# lpc4357-save.net
KiCad netlist of a schematic drawn in Altium Designer
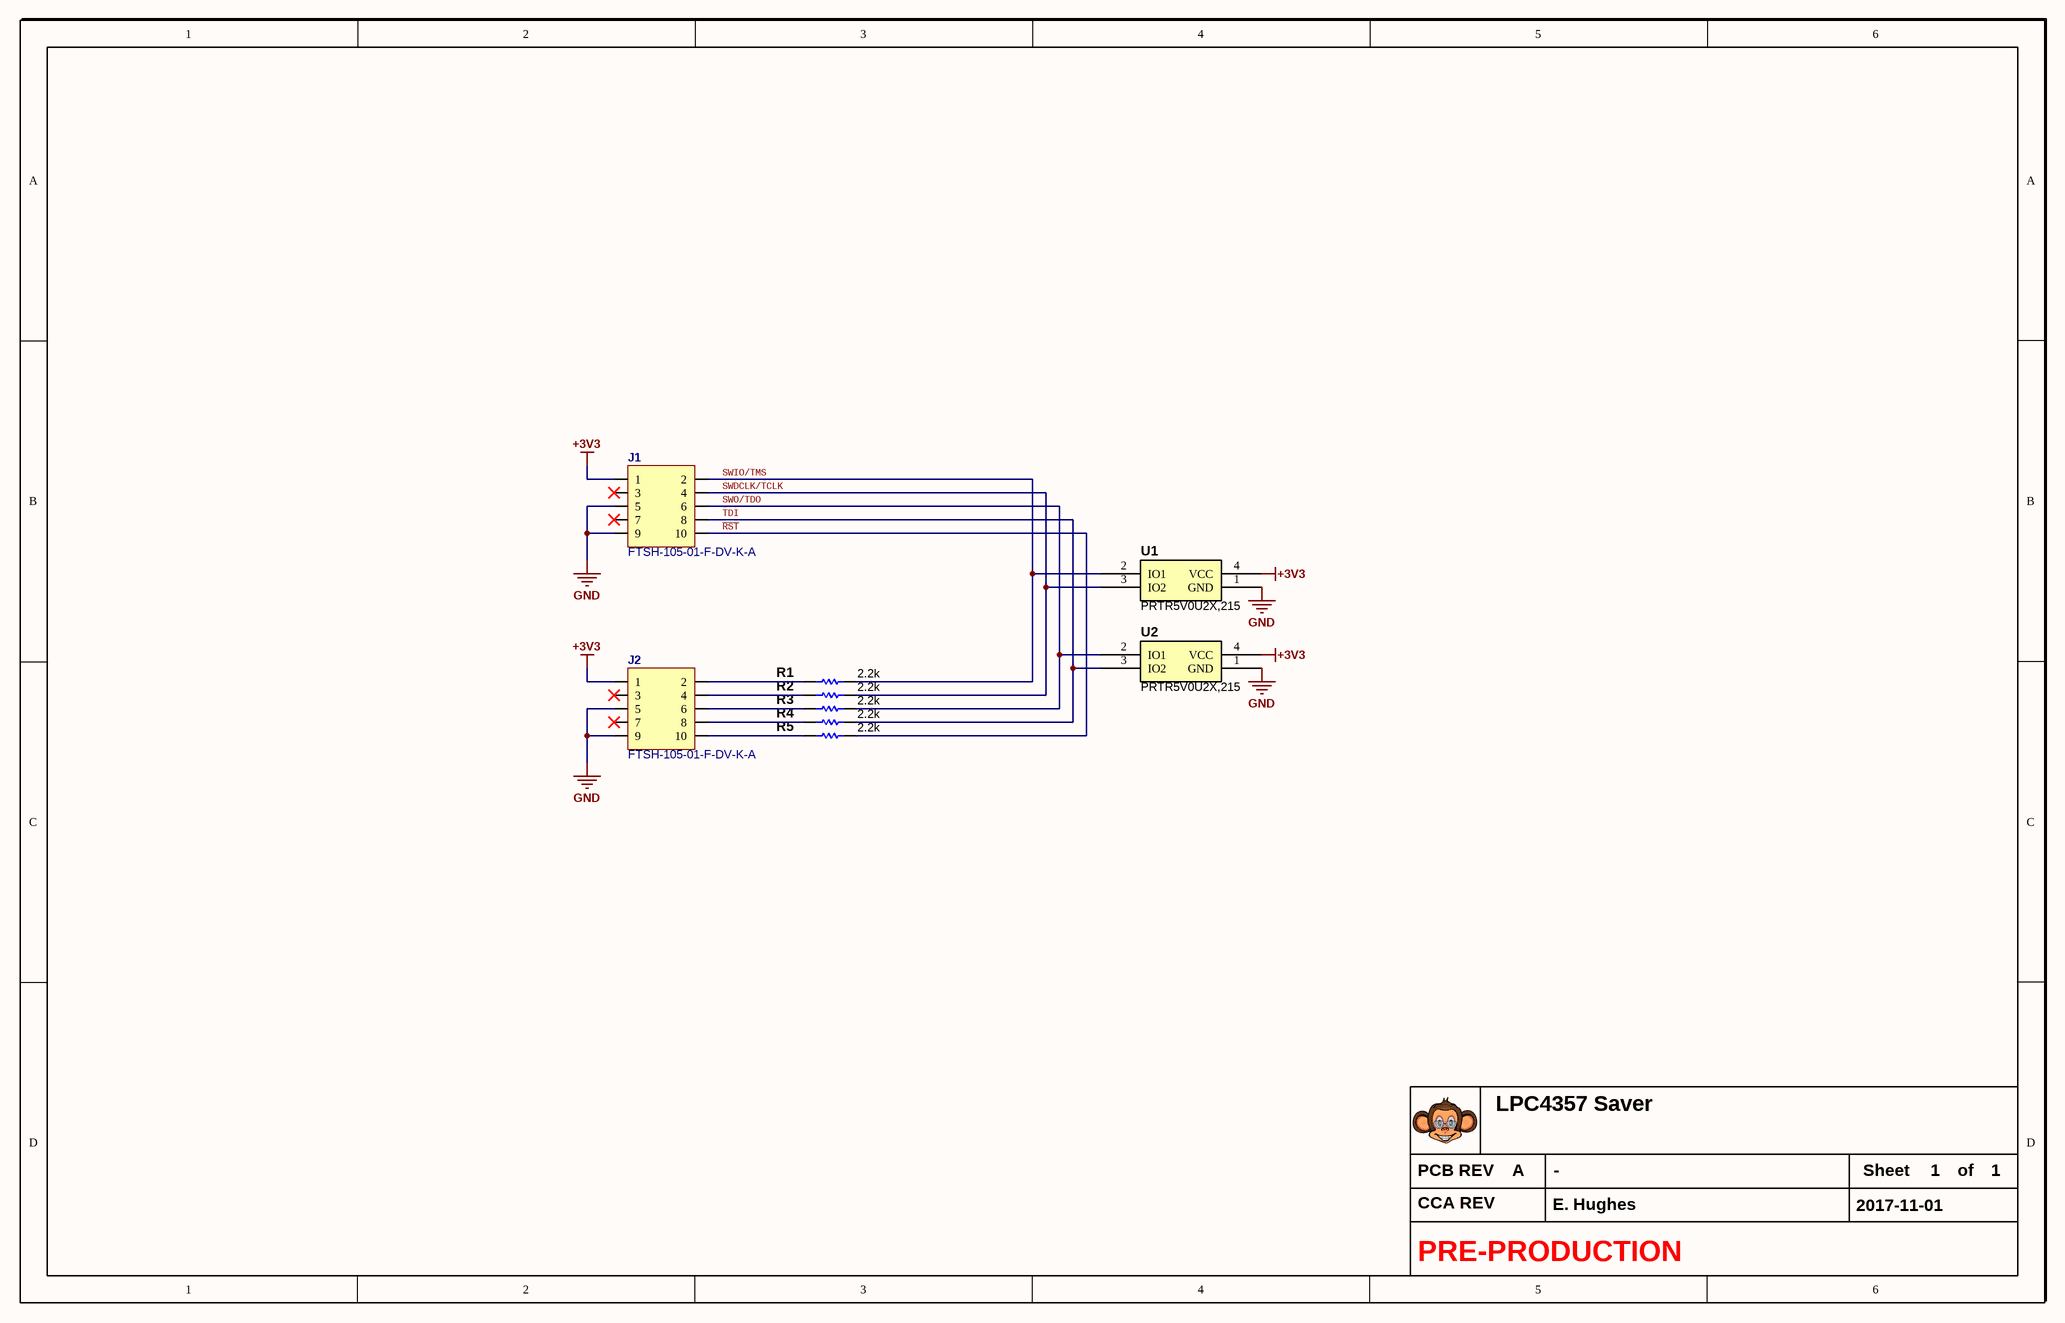
[diagram p0: lpc4357-save.SchDoc]

(export (version "E")
  (design (tool "Eeschema 10.0.6"))
  (components
    (comp (ref "J1")
      (value "FTSH-105-01-F-DV-K-A")
      (footprint "FTSH-105-01-F-DV-K-A")
      (description "CONN HEADER 10POS DUAL .05\" SMD")
      (fields (field (name "MANUFACTURER") "Samtec Inc"))
      (libsource (lib "Samtec-N") (part "FTSH-105-01-F-DV-K-A"))
    )
    (comp (ref "J2")
      (value "FTSH-105-01-F-DV-K-A")
      (footprint "FTSH-105-01-F-DV-K-A")
      (description "CONN HEADER 10POS DUAL .05\" SMD")
      (fields (field (name "MANUFACTURER") "Samtec Inc"))
      (libsource (lib "Samtec-N") (part "FTSH-105-01-F-DV-K-A"))
    )
    (comp (ref "R1")
      (value "2.2k")
      (footprint "R0603_0.55MM_MD")
      (description "RES 2.2K OHM 1/10W 1% 0603 SMD")
      (fields
        (field (name "MANUFACTURER PART NUMBER") "ERJ-3EKF2201V")
        (field (name "MANUFACTURER") "Panasonic Electronic Components")
      )
      (libsource (lib "Resistors - Panasonic - AEC-Q200") (part "R_2P"))
    )
    (comp (ref "R2")
      (value "2.2k")
      (footprint "R0603_0.55MM_MD")
      (description "RES 2.2K OHM 1/10W 1% 0603 SMD")
      (fields
        (field (name "MANUFACTURER PART NUMBER") "ERJ-3EKF2201V")
        (field (name "MANUFACTURER") "Panasonic Electronic Components")
      )
      (libsource (lib "Resistors - Panasonic - AEC-Q200") (part "R_2P"))
    )
    (comp (ref "R3")
      (value "2.2k")
      (footprint "R0603_0.55MM_MD")
      (description "RES 2.2K OHM 1/10W 1% 0603 SMD")
      (fields
        (field (name "MANUFACTURER PART NUMBER") "ERJ-3EKF2201V")
        (field (name "MANUFACTURER") "Panasonic Electronic Components")
      )
      (libsource (lib "Resistors - Panasonic - AEC-Q200") (part "R_2P"))
    )
    (comp (ref "R4")
      (value "2.2k")
      (footprint "R0603_0.55MM_MD")
      (description "RES 2.2K OHM 1/10W 1% 0603 SMD")
      (fields
        (field (name "MANUFACTURER PART NUMBER") "ERJ-3EKF2201V")
        (field (name "MANUFACTURER") "Panasonic Electronic Components")
      )
      (libsource (lib "Resistors - Panasonic - AEC-Q200") (part "R_2P"))
    )
    (comp (ref "R5")
      (value "2.2k")
      (footprint "R0603_0.55MM_MD")
      (description "RES 2.2K OHM 1/10W 1% 0603 SMD")
      (fields
        (field (name "MANUFACTURER PART NUMBER") "ERJ-3EKF2201V")
        (field (name "MANUFACTURER") "Panasonic Electronic Components")
      )
      (libsource (lib "Resistors - Panasonic - AEC-Q200") (part "R_2P"))
    )
    (comp (ref "U1")
      (value "PRTR5V0U2X,215")
      (footprint "SOT143B")
      (description "TVS DIODE 5.5VWM SOT143B")
      (fields (field (name "MANUFACTURER") "NXP Semiconductors"))
      (libsource (lib "eDiode") (part "PRTR5V0U2X,215"))
    )
    (comp (ref "U2")
      (value "PRTR5V0U2X,215")
      (footprint "SOT143B")
      (description "TVS DIODE 5.5VWM SOT143B")
      (fields (field (name "MANUFACTURER") "NXP Semiconductors"))
      (libsource (lib "eDiode") (part "PRTR5V0U2X,215"))
    )
  )
  (nets
    (net (code "1") (name "+3V3") (class "Default")
      (node (ref "J1") (pin "1") (pinfunction "1_1") (pintype "passive"))
      (node (ref "J2") (pin "1") (pinfunction "1_1") (pintype "passive"))
      (node (ref "U1") (pin "4") (pinfunction "VCC_4") (pintype "passive"))
      (node (ref "U2") (pin "4") (pinfunction "VCC_4") (pintype "passive"))
    )
    (net (code "2") (name "/RST") (class "Default")
      (node (ref "J1") (pin "10") (pinfunction "10_10") (pintype "passive"))
      (node (ref "R5") (pin "2") (pinfunction "2_2") (pintype "passive"))
    )
    (net (code "3") (name "/SWDCLK{slash}TCLK") (class "Default")
      (node (ref "J1") (pin "4") (pinfunction "4_4") (pintype "passive"))
      (node (ref "R2") (pin "2") (pinfunction "2_2") (pintype "passive"))
      (node (ref "U1") (pin "3") (pinfunction "IO2_3") (pintype "passive"))
    )
    (net (code "4") (name "/SWIO{slash}TMS") (class "Default")
      (node (ref "J1") (pin "2") (pinfunction "2_2") (pintype "passive"))
      (node (ref "R1") (pin "2") (pinfunction "2_2") (pintype "passive"))
      (node (ref "U1") (pin "2") (pinfunction "IO1_2") (pintype "passive"))
    )
    (net (code "5") (name "/SWO{slash}TDO") (class "Default")
      (node (ref "J1") (pin "6") (pinfunction "6_6") (pintype "passive"))
      (node (ref "R3") (pin "2") (pinfunction "2_2") (pintype "passive"))
      (node (ref "U2") (pin "2") (pinfunction "IO1_2") (pintype "passive"))
    )
    (net (code "6") (name "/TDI") (class "Default")
      (node (ref "J1") (pin "8") (pinfunction "8_8") (pintype "passive"))
      (node (ref "R4") (pin "2") (pinfunction "2_2") (pintype "passive"))
      (node (ref "U2") (pin "3") (pinfunction "IO2_3") (pintype "passive"))
    )
    (net (code "7") (name "GND") (class "Default")
      (node (ref "J1") (pin "5") (pinfunction "5_5") (pintype "passive"))
      (node (ref "J1") (pin "9") (pinfunction "9_9") (pintype "passive"))
      (node (ref "J2") (pin "5") (pinfunction "5_5") (pintype "passive"))
      (node (ref "J2") (pin "9") (pinfunction "9_9") (pintype "passive"))
      (node (ref "U1") (pin "1") (pinfunction "GND_1") (pintype "passive"))
      (node (ref "U2") (pin "1") (pinfunction "GND_1") (pintype "passive"))
    )
    (net (code "8") (name "Net-(J2-Pad2)") (class "Default")
      (node (ref "J2") (pin "2") (pinfunction "2_2") (pintype "passive"))
      (node (ref "R1") (pin "1") (pinfunction "1_1") (pintype "passive"))
    )
    (net (code "9") (name "Net-(J2-Pad4)") (class "Default")
      (node (ref "J2") (pin "4") (pinfunction "4_4") (pintype "passive"))
      (node (ref "R2") (pin "1") (pinfunction "1_1") (pintype "passive"))
    )
    (net (code "10") (name "Net-(J2-Pad6)") (class "Default")
      (node (ref "J2") (pin "6") (pinfunction "6_6") (pintype "passive"))
      (node (ref "R3") (pin "1") (pinfunction "1_1") (pintype "passive"))
    )
    (net (code "11") (name "Net-(J2-Pad8)") (class "Default")
      (node (ref "J2") (pin "8") (pinfunction "8_8") (pintype "passive"))
      (node (ref "R4") (pin "1") (pinfunction "1_1") (pintype "passive"))
    )
    (net (code "12") (name "Net-(J2-Pad10)") (class "Default")
      (node (ref "J2") (pin "10") (pinfunction "10_10") (pintype "passive"))
      (node (ref "R5") (pin "1") (pinfunction "1_1") (pintype "passive"))
    )
    (net (code "13") (name "unconnected-(J1-Pad3)") (class "Default")
      (node (ref "J1") (pin "3") (pinfunction "3_3") (pintype "passive+no_connect"))
    )
    (net (code "14") (name "unconnected-(J1-Pad7)") (class "Default")
      (node (ref "J1") (pin "7") (pinfunction "7_7") (pintype "passive+no_connect"))
    )
    (net (code "15") (name "unconnected-(J2-Pad3)") (class "Default")
      (node (ref "J2") (pin "3") (pinfunction "3_3") (pintype "passive+no_connect"))
    )
    (net (code "16") (name "unconnected-(J2-Pad7)") (class "Default")
      (node (ref "J2") (pin "7") (pinfunction "7_7") (pintype "passive+no_connect"))
    )
  )
)
